# ProjectFile.net
KiCad netlist of a schematic drawn in EAGLE
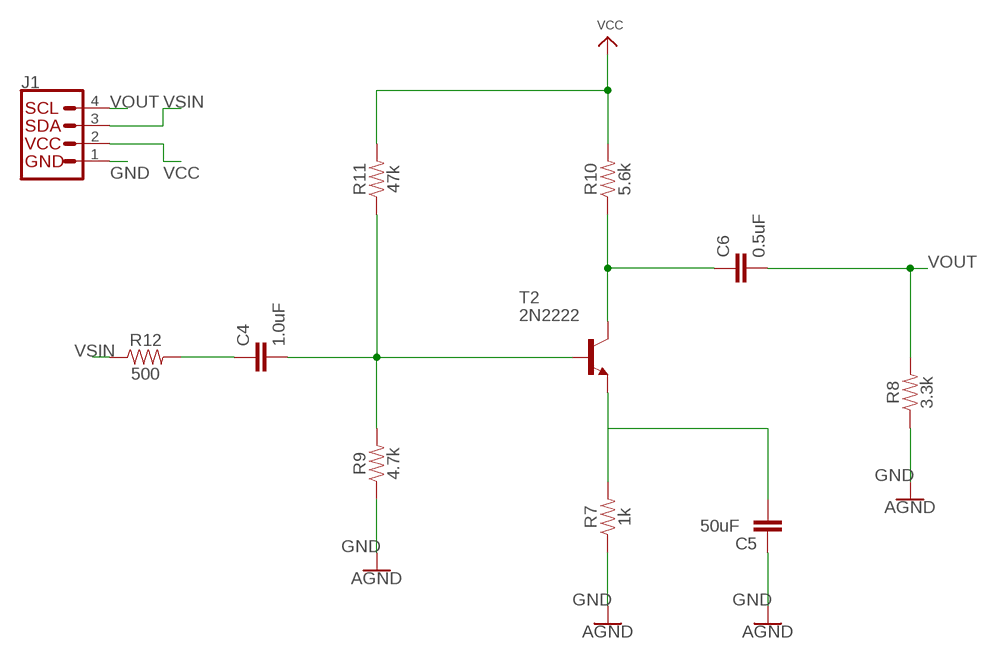
[diagram p0: schematic, sheet 1]

(export (version "E")
  (design (tool "Eeschema 10.0.6"))
  (components
    (comp (ref "C4")
      (value "1.0uF")
      (footprint "eagle-import:0603")
      (libsource (lib "eagle-import") (part "1.0UF-0603-16V-10%"))
    )
    (comp (ref "C5")
      (value "50uF")
      (footprint "eagle-import:0603")
      (libsource (lib "eagle-import") (part "1.0UF-0603-16V-10%"))
    )
    (comp (ref "C6")
      (value "0.5uF")
      (footprint "eagle-import:0603")
      (libsource (lib "eagle-import") (part "1.0UF-0603-16V-10%"))
    )
    (comp (ref "J1")
      (value "QWIIC_CONNECTORJS-1MM")
      (footprint "eagle-import:1X04_1MM_RA")
      (libsource (lib "eagle-import") (part "QWIIC_CONNECTORJS-1MM"))
    )
    (comp (ref "R7")
      (value "1k")
      (footprint "eagle-import:0603")
      (libsource (lib "eagle-import") (part "1KOHM-0603-1/10W-1%"))
    )
    (comp (ref "R8")
      (value "3.3k")
      (footprint "eagle-import:0603")
      (libsource (lib "eagle-import") (part "3.3KOHM-0603-1/10W-1%"))
    )
    (comp (ref "R9")
      (value "4.7k")
      (footprint "eagle-import:0603")
      (libsource (lib "eagle-import") (part "4.7KOHM-0603-1/10W-1%"))
    )
    (comp (ref "R10")
      (value "5.6k")
      (footprint "eagle-import:0603")
      (libsource (lib "eagle-import") (part "5.6KOHM-0603-1/10W-1%"))
    )
    (comp (ref "R11")
      (value "47k")
      (footprint "eagle-import:0603")
      (libsource (lib "eagle-import") (part "47KOHM-0603-1/10W-1%"))
    )
    (comp (ref "R12")
      (value "500")
      (footprint "eagle-import:0603")
      (libsource (lib "eagle-import") (part "300OHM-0603-1/10W-1%"))
    )
    (comp (ref "T2")
      (value "2N2222")
      (footprint "eagle-import:TO92-EBC-OVAL")
      (libsource (lib "eagle-import") (part "2N2222"))
    )
  )
  (nets
    (net (code "1") (name "/VOUT") (class "Default")
      (node (ref "C6") (pin "2") (pinfunction "2_2") (pintype "passive"))
      (node (ref "J1") (pin "4") (pinfunction "SCL_4") (pintype "passive"))
      (node (ref "R8") (pin "2") (pinfunction "2_2") (pintype "passive"))
    )
    (net (code "2") (name "/VSIN") (class "Default")
      (node (ref "J1") (pin "3") (pinfunction "SDA_3") (pintype "passive"))
      (node (ref "R12") (pin "1") (pinfunction "1_1") (pintype "passive"))
    )
    (net (code "3") (name "AGND") (class "Default")
      (node (ref "C5") (pin "1") (pinfunction "1_1") (pintype "passive"))
      (node (ref "J1") (pin "1") (pinfunction "GND_1") (pintype "power_in"))
      (node (ref "R7") (pin "1") (pinfunction "1_1") (pintype "passive"))
      (node (ref "R8") (pin "1") (pinfunction "1_1") (pintype "passive"))
      (node (ref "R9") (pin "1") (pinfunction "1_1") (pintype "passive"))
    )
    (net (code "4") (name "Net-(C4-Pad1)") (class "Default")
      (node (ref "C4") (pin "1") (pinfunction "1_1") (pintype "passive"))
      (node (ref "R12") (pin "2") (pinfunction "2_2") (pintype "passive"))
    )
    (net (code "5") (name "Net-(C4-Pad2)") (class "Default")
      (node (ref "C4") (pin "2") (pinfunction "2_2") (pintype "passive"))
      (node (ref "R11") (pin "1") (pinfunction "1_1") (pintype "passive"))
      (node (ref "R9") (pin "2") (pinfunction "2_2") (pintype "passive"))
      (node (ref "T2") (pin "B") (pinfunction "B_B") (pintype "passive"))
    )
    (net (code "6") (name "Net-(C5-Pad2)") (class "Default")
      (node (ref "C5") (pin "2") (pinfunction "2_2") (pintype "passive"))
      (node (ref "R7") (pin "2") (pinfunction "2_2") (pintype "passive"))
      (node (ref "T2") (pin "E") (pinfunction "E_E") (pintype "passive"))
    )
    (net (code "7") (name "Net-(C6-Pad1)") (class "Default")
      (node (ref "C6") (pin "1") (pinfunction "1_1") (pintype "passive"))
      (node (ref "R10") (pin "1") (pinfunction "1_1") (pintype "passive"))
      (node (ref "T2") (pin "C") (pinfunction "C_C") (pintype "passive"))
    )
    (net (code "8") (name "VCC") (class "Default")
      (node (ref "J1") (pin "2") (pinfunction "VCC_2") (pintype "power_in"))
      (node (ref "R10") (pin "2") (pinfunction "2_2") (pintype "passive"))
      (node (ref "R11") (pin "2") (pinfunction "2_2") (pintype "passive"))
    )
  )
)
